# AccessPanelV4.net
KiCad netlist of a schematic drawn in EAGLE
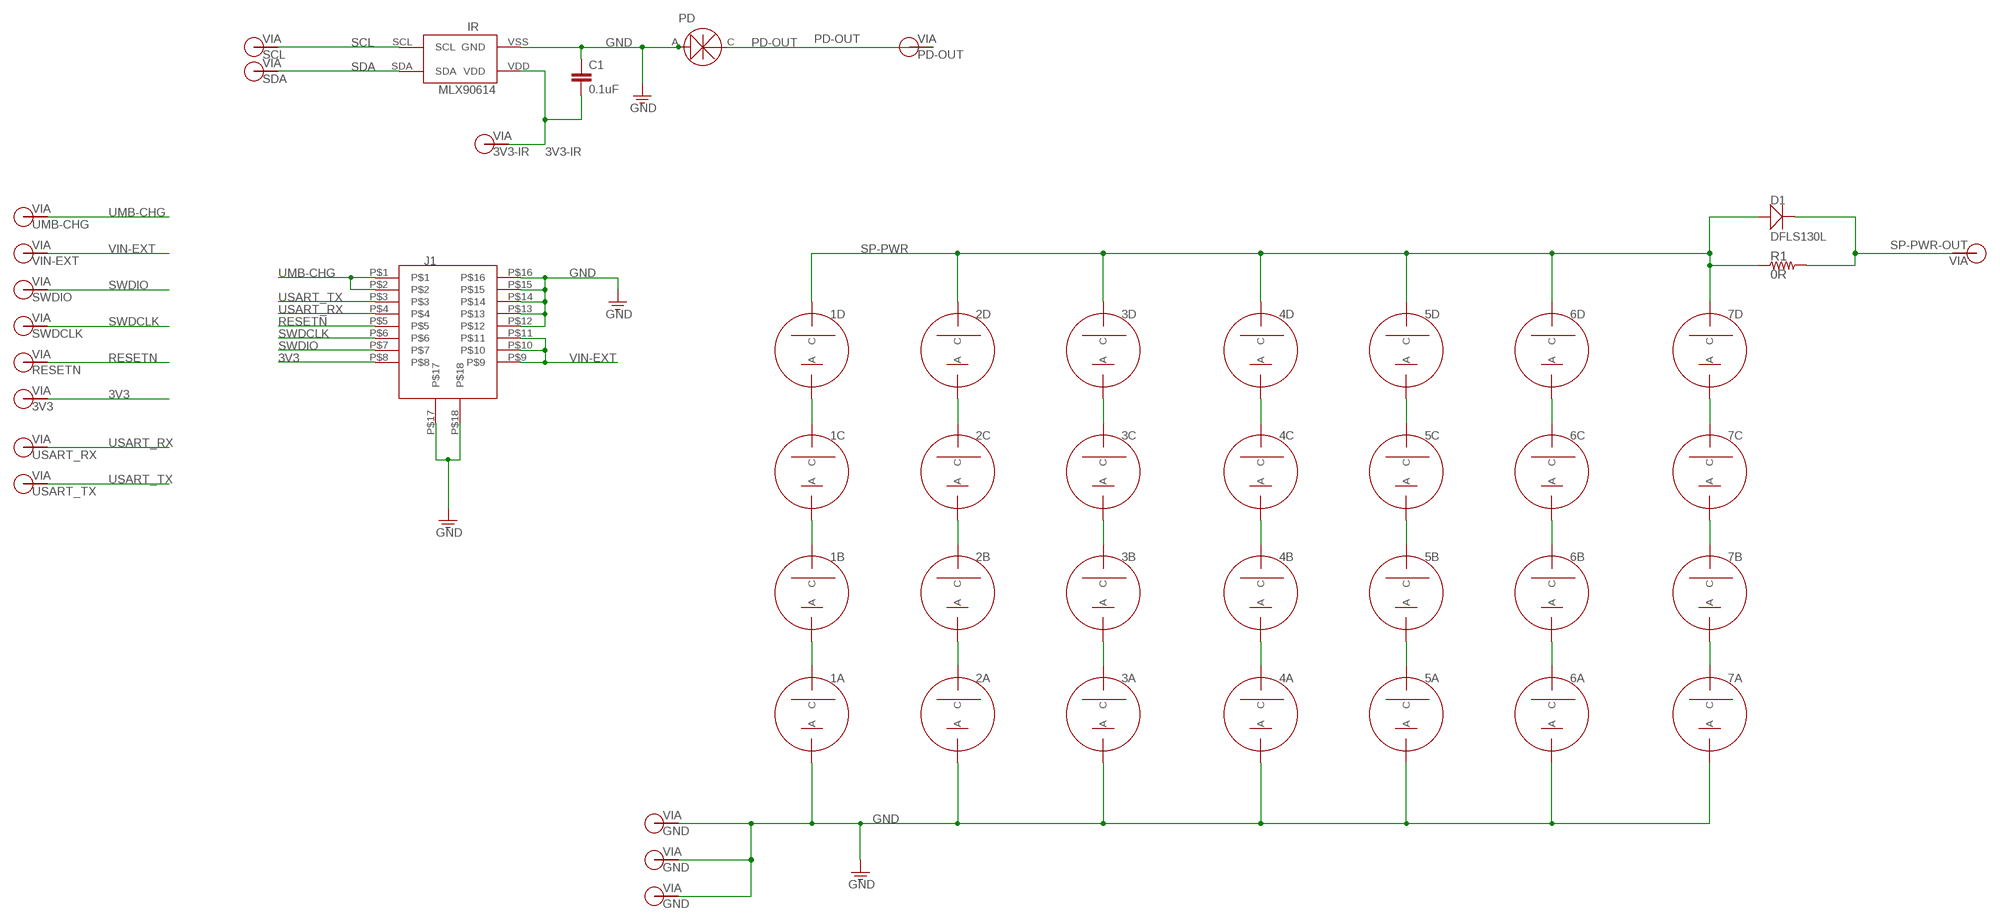
[diagram p0: schematic, sheet 1]

(export (version "E")
  (design (tool "Eeschema 10.0.6"))
  (components
    (comp (ref "1A")
      (value "SOLARCELLV3")
      (footprint "eagle-import:TRISOLX-V3")
      (libsource (lib "eagle-import") (part "SOLARCELLV3"))
    )
    (comp (ref "1B")
      (value "SOLARCELLV3")
      (footprint "eagle-import:TRISOLX-V3")
      (libsource (lib "eagle-import") (part "SOLARCELLV3"))
    )
    (comp (ref "1C")
      (value "SOLARCELLV3")
      (footprint "eagle-import:TRISOLX-V3")
      (libsource (lib "eagle-import") (part "SOLARCELLV3"))
    )
    (comp (ref "1D")
      (value "SOLARCELLV3")
      (footprint "eagle-import:TRISOLX-V3")
      (libsource (lib "eagle-import") (part "SOLARCELLV3"))
    )
    (comp (ref "2A")
      (value "SOLARCELLV3")
      (footprint "eagle-import:TRISOLX-V3")
      (libsource (lib "eagle-import") (part "SOLARCELLV3"))
    )
    (comp (ref "2B")
      (value "SOLARCELLV3")
      (footprint "eagle-import:TRISOLX-V3")
      (libsource (lib "eagle-import") (part "SOLARCELLV3"))
    )
    (comp (ref "2C")
      (value "SOLARCELLV3")
      (footprint "eagle-import:TRISOLX-V3")
      (libsource (lib "eagle-import") (part "SOLARCELLV3"))
    )
    (comp (ref "2D")
      (value "SOLARCELLV3")
      (footprint "eagle-import:TRISOLX-V3")
      (libsource (lib "eagle-import") (part "SOLARCELLV3"))
    )
    (comp (ref "3A")
      (value "SOLARCELLV3")
      (footprint "eagle-import:TRISOLX-V3")
      (libsource (lib "eagle-import") (part "SOLARCELLV3"))
    )
    (comp (ref "3B")
      (value "SOLARCELLV3")
      (footprint "eagle-import:TRISOLX-V3")
      (libsource (lib "eagle-import") (part "SOLARCELLV3"))
    )
    (comp (ref "3C")
      (value "SOLARCELLV3")
      (footprint "eagle-import:TRISOLX-V3")
      (libsource (lib "eagle-import") (part "SOLARCELLV3"))
    )
    (comp (ref "3D")
      (value "SOLARCELLV3")
      (footprint "eagle-import:TRISOLX-V3")
      (libsource (lib "eagle-import") (part "SOLARCELLV3"))
    )
    (comp (ref "4A")
      (value "SOLARCELLV3")
      (footprint "eagle-import:TRISOLX-V3")
      (libsource (lib "eagle-import") (part "SOLARCELLV3"))
    )
    (comp (ref "4B")
      (value "SOLARCELLV3")
      (footprint "eagle-import:TRISOLX-V3")
      (libsource (lib "eagle-import") (part "SOLARCELLV3"))
    )
    (comp (ref "4C")
      (value "SOLARCELLV3")
      (footprint "eagle-import:TRISOLX-V3")
      (libsource (lib "eagle-import") (part "SOLARCELLV3"))
    )
    (comp (ref "4D")
      (value "SOLARCELLV3")
      (footprint "eagle-import:TRISOLX-V3")
      (libsource (lib "eagle-import") (part "SOLARCELLV3"))
    )
    (comp (ref "5A")
      (value "SOLARCELLV3")
      (footprint "eagle-import:TRISOLX-V3")
      (libsource (lib "eagle-import") (part "SOLARCELLV3"))
    )
    (comp (ref "5B")
      (value "SOLARCELLV3")
      (footprint "eagle-import:TRISOLX-V3")
      (libsource (lib "eagle-import") (part "SOLARCELLV3"))
    )
    (comp (ref "5C")
      (value "SOLARCELLV3")
      (footprint "eagle-import:TRISOLX-V3")
      (libsource (lib "eagle-import") (part "SOLARCELLV3"))
    )
    (comp (ref "5D")
      (value "SOLARCELLV3")
      (footprint "eagle-import:TRISOLX-V3")
      (libsource (lib "eagle-import") (part "SOLARCELLV3"))
    )
    (comp (ref "6A")
      (value "SOLARCELLV3")
      (footprint "eagle-import:TRISOLX-V3")
      (libsource (lib "eagle-import") (part "SOLARCELLV3"))
    )
    (comp (ref "6B")
      (value "SOLARCELLV3")
      (footprint "eagle-import:TRISOLX-V3")
      (libsource (lib "eagle-import") (part "SOLARCELLV3"))
    )
    (comp (ref "6C")
      (value "SOLARCELLV3")
      (footprint "eagle-import:TRISOLX-V3")
      (libsource (lib "eagle-import") (part "SOLARCELLV3"))
    )
    (comp (ref "6D")
      (value "SOLARCELLV3")
      (footprint "eagle-import:TRISOLX-V3")
      (libsource (lib "eagle-import") (part "SOLARCELLV3"))
    )
    (comp (ref "7A")
      (value "SOLARCELLV3")
      (footprint "eagle-import:TRISOLX-V3")
      (libsource (lib "eagle-import") (part "SOLARCELLV3"))
    )
    (comp (ref "7B")
      (value "SOLARCELLV3")
      (footprint "eagle-import:TRISOLX-V3")
      (libsource (lib "eagle-import") (part "SOLARCELLV3"))
    )
    (comp (ref "7C")
      (value "SOLARCELLV3")
      (footprint "eagle-import:TRISOLX-V3")
      (libsource (lib "eagle-import") (part "SOLARCELLV3"))
    )
    (comp (ref "7D")
      (value "SOLARCELLV3")
      (footprint "eagle-import:TRISOLX-V3")
      (libsource (lib "eagle-import") (part "SOLARCELLV3"))
    )
    (comp (ref "C1")
      (value "0.1uF")
      (footprint "eagle-import:0805")
      (libsource (lib "eagle-import") (part "CAP0805"))
    )
    (comp (ref "D1")
      (value "DFLS130L")
      (footprint "eagle-import:PWRDI-123")
      (libsource (lib "eagle-import") (part "DFLS130L"))
    )
    (comp (ref "IR")
      (value "MXL90614")
      (footprint "eagle-import:MXL90620")
      (libsource (lib "eagle-import") (part "MXL90614"))
    )
    (comp (ref "J1")
      (value "FFC-16")
      (footprint "eagle-import:68611614422")
      (libsource (lib "eagle-import") (part "FFC-16"))
    )
    (comp (ref "PD")
      (value "TEMD6200")
      (footprint "eagle-import:TEMD6200")
      (libsource (lib "eagle-import") (part "TEMD6200"))
    )
    (comp (ref "R1")
      (value "0R")
      (footprint "eagle-import:1210")
      (libsource (lib "eagle-import") (part "RES1210"))
    )
    (comp (ref "SCL")
      (value "SCL")
      (footprint "eagle-import:VIA-60MIL")
      (libsource (lib "eagle-import") (part "VIA-60MIL"))
    )
    (comp (ref "SDA")
      (value "SDA")
      (footprint "eagle-import:VIA-60MIL")
      (libsource (lib "eagle-import") (part "VIA-60MIL"))
    )
    (comp (ref "V1")
      (value "SP-PWR-OUT")
      (footprint "eagle-import:VIA-60MIL")
      (libsource (lib "eagle-import") (part "VIA-60MIL"))
    )
    (comp (ref "V2")
      (value "GND")
      (footprint "eagle-import:VIA-60MIL")
      (libsource (lib "eagle-import") (part "VIA-60MIL"))
    )
    (comp (ref "V3")
      (value "3V3-IR")
      (footprint "eagle-import:VIA-60MIL")
      (libsource (lib "eagle-import") (part "VIA-60MIL"))
    )
    (comp (ref "V4")
      (value "GND")
      (footprint "eagle-import:VIA-60MIL")
      (libsource (lib "eagle-import") (part "VIA-60MIL"))
    )
    (comp (ref "V5")
      (value "GND")
      (footprint "eagle-import:VIA-60MIL")
      (libsource (lib "eagle-import") (part "VIA-60MIL"))
    )
    (comp (ref "V6")
      (value "PD-OUT")
      (footprint "eagle-import:VIA-60MIL")
      (libsource (lib "eagle-import") (part "VIA-60MIL"))
    )
    (comp (ref "V7")
      (value "UMB-CHG")
      (footprint "eagle-import:VIA-60MIL")
      (libsource (lib "eagle-import") (part "VIA-60MIL"))
    )
    (comp (ref "V8")
      (value "VIN-EXT")
      (footprint "eagle-import:VIA-60MIL")
      (libsource (lib "eagle-import") (part "VIA-60MIL"))
    )
    (comp (ref "V9")
      (value "SWDIO")
      (footprint "eagle-import:VIA-60MIL")
      (libsource (lib "eagle-import") (part "VIA-60MIL"))
    )
    (comp (ref "V10")
      (value "SWDCLK")
      (footprint "eagle-import:VIA-60MIL")
      (libsource (lib "eagle-import") (part "VIA-60MIL"))
    )
    (comp (ref "V11")
      (value "RESETN")
      (footprint "eagle-import:VIA-60MIL")
      (libsource (lib "eagle-import") (part "VIA-60MIL"))
    )
    (comp (ref "V14")
      (value "USART_RX")
      (footprint "eagle-import:VIA-60MIL")
      (libsource (lib "eagle-import") (part "VIA-60MIL"))
    )
    (comp (ref "V15")
      (value "USART_TX")
      (footprint "eagle-import:VIA-60MIL")
      (libsource (lib "eagle-import") (part "VIA-60MIL"))
    )
    (comp (ref "V16")
      (value "3V3")
      (footprint "eagle-import:VIA-60MIL")
      (libsource (lib "eagle-import") (part "VIA-60MIL"))
    )
  )
  (nets
    (net (code "1") (name "/3V3") (class "Default")
      (node (ref "J1") (pin "P$8") (pinfunction "P$8_P$8") (pintype "bidirectional"))
      (node (ref "V16") (pin "P$1") (pinfunction "P$1_P$1") (pintype "bidirectional"))
    )
    (net (code "2") (name "/3V3-IR") (class "Default")
      (node (ref "C1") (pin "2") (pinfunction "2_2") (pintype "passive"))
      (node (ref "IR") (pin "VDD") (pinfunction "VDD_VDD") (pintype "bidirectional"))
      (node (ref "V3") (pin "P$1") (pinfunction "P$1_P$1") (pintype "bidirectional"))
    )
    (net (code "3") (name "/PD-OUT") (class "Default")
      (node (ref "PD") (pin "C") (pinfunction "C_C") (pintype "bidirectional"))
      (node (ref "V6") (pin "P$1") (pinfunction "P$1_P$1") (pintype "bidirectional"))
    )
    (net (code "4") (name "/RESETN") (class "Default")
      (node (ref "J1") (pin "P$5") (pinfunction "P$5_P$5") (pintype "bidirectional"))
      (node (ref "V11") (pin "P$1") (pinfunction "P$1_P$1") (pintype "bidirectional"))
    )
    (net (code "5") (name "/SCL") (class "Default")
      (node (ref "IR") (pin "SCL") (pinfunction "SCL_SCL") (pintype "bidirectional"))
      (node (ref "SCL") (pin "P$1") (pinfunction "P$1_P$1") (pintype "bidirectional"))
    )
    (net (code "6") (name "/SDA") (class "Default")
      (node (ref "IR") (pin "SDA") (pinfunction "SDA_SDA") (pintype "bidirectional"))
      (node (ref "SDA") (pin "P$1") (pinfunction "P$1_P$1") (pintype "bidirectional"))
    )
    (net (code "7") (name "/SP-PWR") (class "Default")
      (node (ref "1D") (pin "CATHODE") (pinfunction "C_CATHODE") (pintype "bidirectional"))
      (node (ref "2D") (pin "CATHODE") (pinfunction "C_CATHODE") (pintype "bidirectional"))
      (node (ref "3D") (pin "CATHODE") (pinfunction "C_CATHODE") (pintype "bidirectional"))
      (node (ref "4D") (pin "CATHODE") (pinfunction "C_CATHODE") (pintype "bidirectional"))
      (node (ref "5D") (pin "CATHODE") (pinfunction "C_CATHODE") (pintype "bidirectional"))
      (node (ref "6D") (pin "CATHODE") (pinfunction "C_CATHODE") (pintype "bidirectional"))
      (node (ref "7D") (pin "CATHODE") (pinfunction "C_CATHODE") (pintype "bidirectional"))
      (node (ref "D1") (pin "A") (pinfunction "A_A") (pintype "bidirectional"))
      (node (ref "R1") (pin "P$1") (pinfunction "1_P$1") (pintype "passive"))
    )
    (net (code "8") (name "/SWDCLK") (class "Default")
      (node (ref "J1") (pin "P$6") (pinfunction "P$6_P$6") (pintype "bidirectional"))
      (node (ref "V10") (pin "P$1") (pinfunction "P$1_P$1") (pintype "bidirectional"))
    )
    (net (code "9") (name "/SWDIO") (class "Default")
      (node (ref "J1") (pin "P$7") (pinfunction "P$7_P$7") (pintype "bidirectional"))
      (node (ref "V9") (pin "P$1") (pinfunction "P$1_P$1") (pintype "bidirectional"))
    )
    (net (code "10") (name "/UMB-CHG") (class "Default")
      (node (ref "J1") (pin "P$1") (pinfunction "P$1_P$1") (pintype "bidirectional"))
      (node (ref "J1") (pin "P$2") (pinfunction "P$2_P$2") (pintype "bidirectional"))
      (node (ref "V7") (pin "P$1") (pinfunction "P$1_P$1") (pintype "bidirectional"))
    )
    (net (code "11") (name "/USART_RX") (class "Default")
      (node (ref "J1") (pin "P$4") (pinfunction "P$4_P$4") (pintype "bidirectional"))
      (node (ref "V14") (pin "P$1") (pinfunction "P$1_P$1") (pintype "bidirectional"))
    )
    (net (code "12") (name "/USART_TX") (class "Default")
      (node (ref "J1") (pin "P$3") (pinfunction "P$3_P$3") (pintype "bidirectional"))
      (node (ref "V15") (pin "P$1") (pinfunction "P$1_P$1") (pintype "bidirectional"))
    )
    (net (code "13") (name "/VIN-EXT") (class "Default")
      (node (ref "J1") (pin "P$10") (pinfunction "P$10_P$10") (pintype "bidirectional"))
      (node (ref "J1") (pin "P$11") (pinfunction "P$11_P$11") (pintype "bidirectional"))
      (node (ref "J1") (pin "P$9") (pinfunction "P$9_P$9") (pintype "bidirectional"))
      (node (ref "V8") (pin "P$1") (pinfunction "P$1_P$1") (pintype "bidirectional"))
    )
    (net (code "14") (name "GND") (class "Default")
      (node (ref "1A") (pin "ANODE") (pinfunction "A_ANODE") (pintype "bidirectional"))
      (node (ref "2A") (pin "ANODE") (pinfunction "A_ANODE") (pintype "bidirectional"))
      (node (ref "3A") (pin "ANODE") (pinfunction "A_ANODE") (pintype "bidirectional"))
      (node (ref "4A") (pin "ANODE") (pinfunction "A_ANODE") (pintype "bidirectional"))
      (node (ref "5A") (pin "ANODE") (pinfunction "A_ANODE") (pintype "bidirectional"))
      (node (ref "6A") (pin "ANODE") (pinfunction "A_ANODE") (pintype "bidirectional"))
      (node (ref "7A") (pin "ANODE") (pinfunction "A_ANODE") (pintype "bidirectional"))
      (node (ref "C1") (pin "1") (pinfunction "1_1") (pintype "passive"))
      (node (ref "IR") (pin "VSS") (pinfunction "GND_VSS") (pintype "bidirectional"))
      (node (ref "J1") (pin "P$12") (pinfunction "P$12_P$12") (pintype "bidirectional"))
      (node (ref "J1") (pin "P$13") (pinfunction "P$13_P$13") (pintype "bidirectional"))
      (node (ref "J1") (pin "P$14") (pinfunction "P$14_P$14") (pintype "bidirectional"))
      (node (ref "J1") (pin "P$15") (pinfunction "P$15_P$15") (pintype "bidirectional"))
      (node (ref "J1") (pin "P$16") (pinfunction "P$16_P$16") (pintype "bidirectional"))
      (node (ref "J1") (pin "P$17") (pinfunction "P$17_P$17") (pintype "bidirectional"))
      (node (ref "J1") (pin "P$18") (pinfunction "P$18_P$18") (pintype "bidirectional"))
      (node (ref "PD") (pin "A") (pinfunction "A_A") (pintype "bidirectional"))
      (node (ref "V2") (pin "P$1") (pinfunction "P$1_P$1") (pintype "bidirectional"))
      (node (ref "V4") (pin "P$1") (pinfunction "P$1_P$1") (pintype "bidirectional"))
      (node (ref "V5") (pin "P$1") (pinfunction "P$1_P$1") (pintype "bidirectional"))
    )
    (net (code "15") (name "Net-(1A-C)") (class "Default")
      (node (ref "1A") (pin "CATHODE") (pinfunction "C_CATHODE") (pintype "bidirectional"))
      (node (ref "1B") (pin "ANODE") (pinfunction "A_ANODE") (pintype "bidirectional"))
    )
    (net (code "16") (name "Net-(1B-C)") (class "Default")
      (node (ref "1B") (pin "CATHODE") (pinfunction "C_CATHODE") (pintype "bidirectional"))
      (node (ref "1C") (pin "ANODE") (pinfunction "A_ANODE") (pintype "bidirectional"))
    )
    (net (code "17") (name "Net-(1C-C)") (class "Default")
      (node (ref "1C") (pin "CATHODE") (pinfunction "C_CATHODE") (pintype "bidirectional"))
      (node (ref "1D") (pin "ANODE") (pinfunction "A_ANODE") (pintype "bidirectional"))
    )
    (net (code "18") (name "Net-(2A-C)") (class "Default")
      (node (ref "2A") (pin "CATHODE") (pinfunction "C_CATHODE") (pintype "bidirectional"))
      (node (ref "2B") (pin "ANODE") (pinfunction "A_ANODE") (pintype "bidirectional"))
    )
    (net (code "19") (name "Net-(2B-C)") (class "Default")
      (node (ref "2B") (pin "CATHODE") (pinfunction "C_CATHODE") (pintype "bidirectional"))
      (node (ref "2C") (pin "ANODE") (pinfunction "A_ANODE") (pintype "bidirectional"))
    )
    (net (code "20") (name "Net-(2C-C)") (class "Default")
      (node (ref "2C") (pin "CATHODE") (pinfunction "C_CATHODE") (pintype "bidirectional"))
      (node (ref "2D") (pin "ANODE") (pinfunction "A_ANODE") (pintype "bidirectional"))
    )
    (net (code "21") (name "Net-(3A-C)") (class "Default")
      (node (ref "3A") (pin "CATHODE") (pinfunction "C_CATHODE") (pintype "bidirectional"))
      (node (ref "3B") (pin "ANODE") (pinfunction "A_ANODE") (pintype "bidirectional"))
    )
    (net (code "22") (name "Net-(3B-C)") (class "Default")
      (node (ref "3B") (pin "CATHODE") (pinfunction "C_CATHODE") (pintype "bidirectional"))
      (node (ref "3C") (pin "ANODE") (pinfunction "A_ANODE") (pintype "bidirectional"))
    )
    (net (code "23") (name "Net-(3C-C)") (class "Default")
      (node (ref "3C") (pin "CATHODE") (pinfunction "C_CATHODE") (pintype "bidirectional"))
      (node (ref "3D") (pin "ANODE") (pinfunction "A_ANODE") (pintype "bidirectional"))
    )
    (net (code "24") (name "Net-(4A-C)") (class "Default")
      (node (ref "4A") (pin "CATHODE") (pinfunction "C_CATHODE") (pintype "bidirectional"))
      (node (ref "4B") (pin "ANODE") (pinfunction "A_ANODE") (pintype "bidirectional"))
    )
    (net (code "25") (name "Net-(4B-C)") (class "Default")
      (node (ref "4B") (pin "CATHODE") (pinfunction "C_CATHODE") (pintype "bidirectional"))
      (node (ref "4C") (pin "ANODE") (pinfunction "A_ANODE") (pintype "bidirectional"))
    )
    (net (code "26") (name "Net-(4C-C)") (class "Default")
      (node (ref "4C") (pin "CATHODE") (pinfunction "C_CATHODE") (pintype "bidirectional"))
      (node (ref "4D") (pin "ANODE") (pinfunction "A_ANODE") (pintype "bidirectional"))
    )
    (net (code "27") (name "Net-(5A-C)") (class "Default")
      (node (ref "5A") (pin "CATHODE") (pinfunction "C_CATHODE") (pintype "bidirectional"))
      (node (ref "5B") (pin "ANODE") (pinfunction "A_ANODE") (pintype "bidirectional"))
    )
    (net (code "28") (name "Net-(5B-C)") (class "Default")
      (node (ref "5B") (pin "CATHODE") (pinfunction "C_CATHODE") (pintype "bidirectional"))
      (node (ref "5C") (pin "ANODE") (pinfunction "A_ANODE") (pintype "bidirectional"))
    )
    (net (code "29") (name "Net-(5C-C)") (class "Default")
      (node (ref "5C") (pin "CATHODE") (pinfunction "C_CATHODE") (pintype "bidirectional"))
      (node (ref "5D") (pin "ANODE") (pinfunction "A_ANODE") (pintype "bidirectional"))
    )
    (net (code "30") (name "Net-(6A-C)") (class "Default")
      (node (ref "6A") (pin "CATHODE") (pinfunction "C_CATHODE") (pintype "bidirectional"))
      (node (ref "6B") (pin "ANODE") (pinfunction "A_ANODE") (pintype "bidirectional"))
    )
    (net (code "31") (name "Net-(6B-C)") (class "Default")
      (node (ref "6B") (pin "CATHODE") (pinfunction "C_CATHODE") (pintype "bidirectional"))
      (node (ref "6C") (pin "ANODE") (pinfunction "A_ANODE") (pintype "bidirectional"))
    )
    (net (code "32") (name "Net-(6C-C)") (class "Default")
      (node (ref "6C") (pin "CATHODE") (pinfunction "C_CATHODE") (pintype "bidirectional"))
      (node (ref "6D") (pin "ANODE") (pinfunction "A_ANODE") (pintype "bidirectional"))
    )
    (net (code "33") (name "Net-(7A-C)") (class "Default")
      (node (ref "7A") (pin "CATHODE") (pinfunction "C_CATHODE") (pintype "bidirectional"))
      (node (ref "7B") (pin "ANODE") (pinfunction "A_ANODE") (pintype "bidirectional"))
    )
    (net (code "34") (name "Net-(7B-C)") (class "Default")
      (node (ref "7B") (pin "CATHODE") (pinfunction "C_CATHODE") (pintype "bidirectional"))
      (node (ref "7C") (pin "ANODE") (pinfunction "A_ANODE") (pintype "bidirectional"))
    )
    (net (code "35") (name "Net-(7C-C)") (class "Default")
      (node (ref "7C") (pin "CATHODE") (pinfunction "C_CATHODE") (pintype "bidirectional"))
      (node (ref "7D") (pin "ANODE") (pinfunction "A_ANODE") (pintype "bidirectional"))
    )
    (net (code "36") (name "Net-(R1-2)") (class "Default")
      (node (ref "D1") (pin "C") (pinfunction "C_C") (pintype "bidirectional"))
      (node (ref "R1") (pin "P$2") (pinfunction "2_P$2") (pintype "passive"))
      (node (ref "V1") (pin "P$1") (pinfunction "P$1_P$1") (pintype "bidirectional"))
    )
  )
)
